# pmod-qwiic.net
KiCad netlist of a schematic drawn in EAGLE
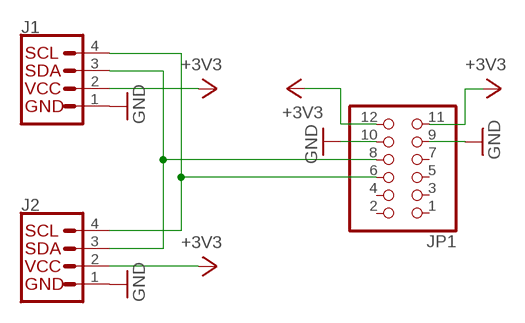
[diagram p0: schematic, sheet 1]

(export (version "E")
  (design (tool "Eeschema 10.0.6"))
  (components
    (comp (ref "J1")
      (value "QWIIC_CONNECTORJS-1MM")
      (footprint "eagle-import:1X04_1MM_RA")
      (libsource (lib "eagle-import") (part "QWIIC_CONNECTORJS-1MM"))
    )
    (comp (ref "J2")
      (value "QWIIC_CONNECTORJS-1MM")
      (footprint "eagle-import:1X04_1MM_RA")
      (libsource (lib "eagle-import") (part "QWIIC_CONNECTORJS-1MM"))
    )
    (comp (ref "JP1")
      (value "PINHD-2X6/90")
      (footprint "eagle-import:2X06_90")
      (libsource (lib "eagle-import") (part "PINHD-2X6/90"))
    )
  )
  (nets
    (net (code "1") (name "+3V3") (class "Default")
      (node (ref "J1") (pin "2") (pinfunction "VCC_2") (pintype "power_in"))
      (node (ref "J2") (pin "2") (pinfunction "VCC_2") (pintype "power_in"))
      (node (ref "JP1") (pin "11") (pinfunction "11_11") (pintype "passive"))
      (node (ref "JP1") (pin "12") (pinfunction "12_12") (pintype "passive"))
    )
    (net (code "2") (name "GND") (class "Default")
      (node (ref "J1") (pin "1") (pinfunction "GND_1") (pintype "power_in"))
      (node (ref "J2") (pin "1") (pinfunction "GND_1") (pintype "power_in"))
      (node (ref "JP1") (pin "10") (pinfunction "10_10") (pintype "passive"))
      (node (ref "JP1") (pin "9") (pinfunction "9_9") (pintype "passive"))
    )
    (net (code "3") (name "Net-(J1-SCL)") (class "Default")
      (node (ref "J1") (pin "4") (pinfunction "SCL_4") (pintype "passive"))
      (node (ref "J2") (pin "4") (pinfunction "SCL_4") (pintype "passive"))
      (node (ref "JP1") (pin "6") (pinfunction "6_6") (pintype "passive"))
    )
    (net (code "4") (name "Net-(J1-SDA)") (class "Default")
      (node (ref "J1") (pin "3") (pinfunction "SDA_3") (pintype "passive"))
      (node (ref "J2") (pin "3") (pinfunction "SDA_3") (pintype "passive"))
      (node (ref "JP1") (pin "8") (pinfunction "8_8") (pintype "passive"))
    )
    (net (code "5") (name "unconnected-(JP1-Pad1)") (class "Default")
      (node (ref "JP1") (pin "1") (pinfunction "1_1") (pintype "passive"))
    )
    (net (code "6") (name "unconnected-(JP1-Pad2)") (class "Default")
      (node (ref "JP1") (pin "2") (pinfunction "2_2") (pintype "passive"))
    )
    (net (code "7") (name "unconnected-(JP1-Pad3)") (class "Default")
      (node (ref "JP1") (pin "3") (pinfunction "3_3") (pintype "passive"))
    )
    (net (code "8") (name "unconnected-(JP1-Pad4)") (class "Default")
      (node (ref "JP1") (pin "4") (pinfunction "4_4") (pintype "passive"))
    )
    (net (code "9") (name "unconnected-(JP1-Pad5)") (class "Default")
      (node (ref "JP1") (pin "5") (pinfunction "5_5") (pintype "passive"))
    )
    (net (code "10") (name "unconnected-(JP1-Pad7)") (class "Default")
      (node (ref "JP1") (pin "7") (pinfunction "7_7") (pintype "passive"))
    )
  )
)
